# BSPD_5.net
KiCad netlist of a schematic drawn in EAGLE
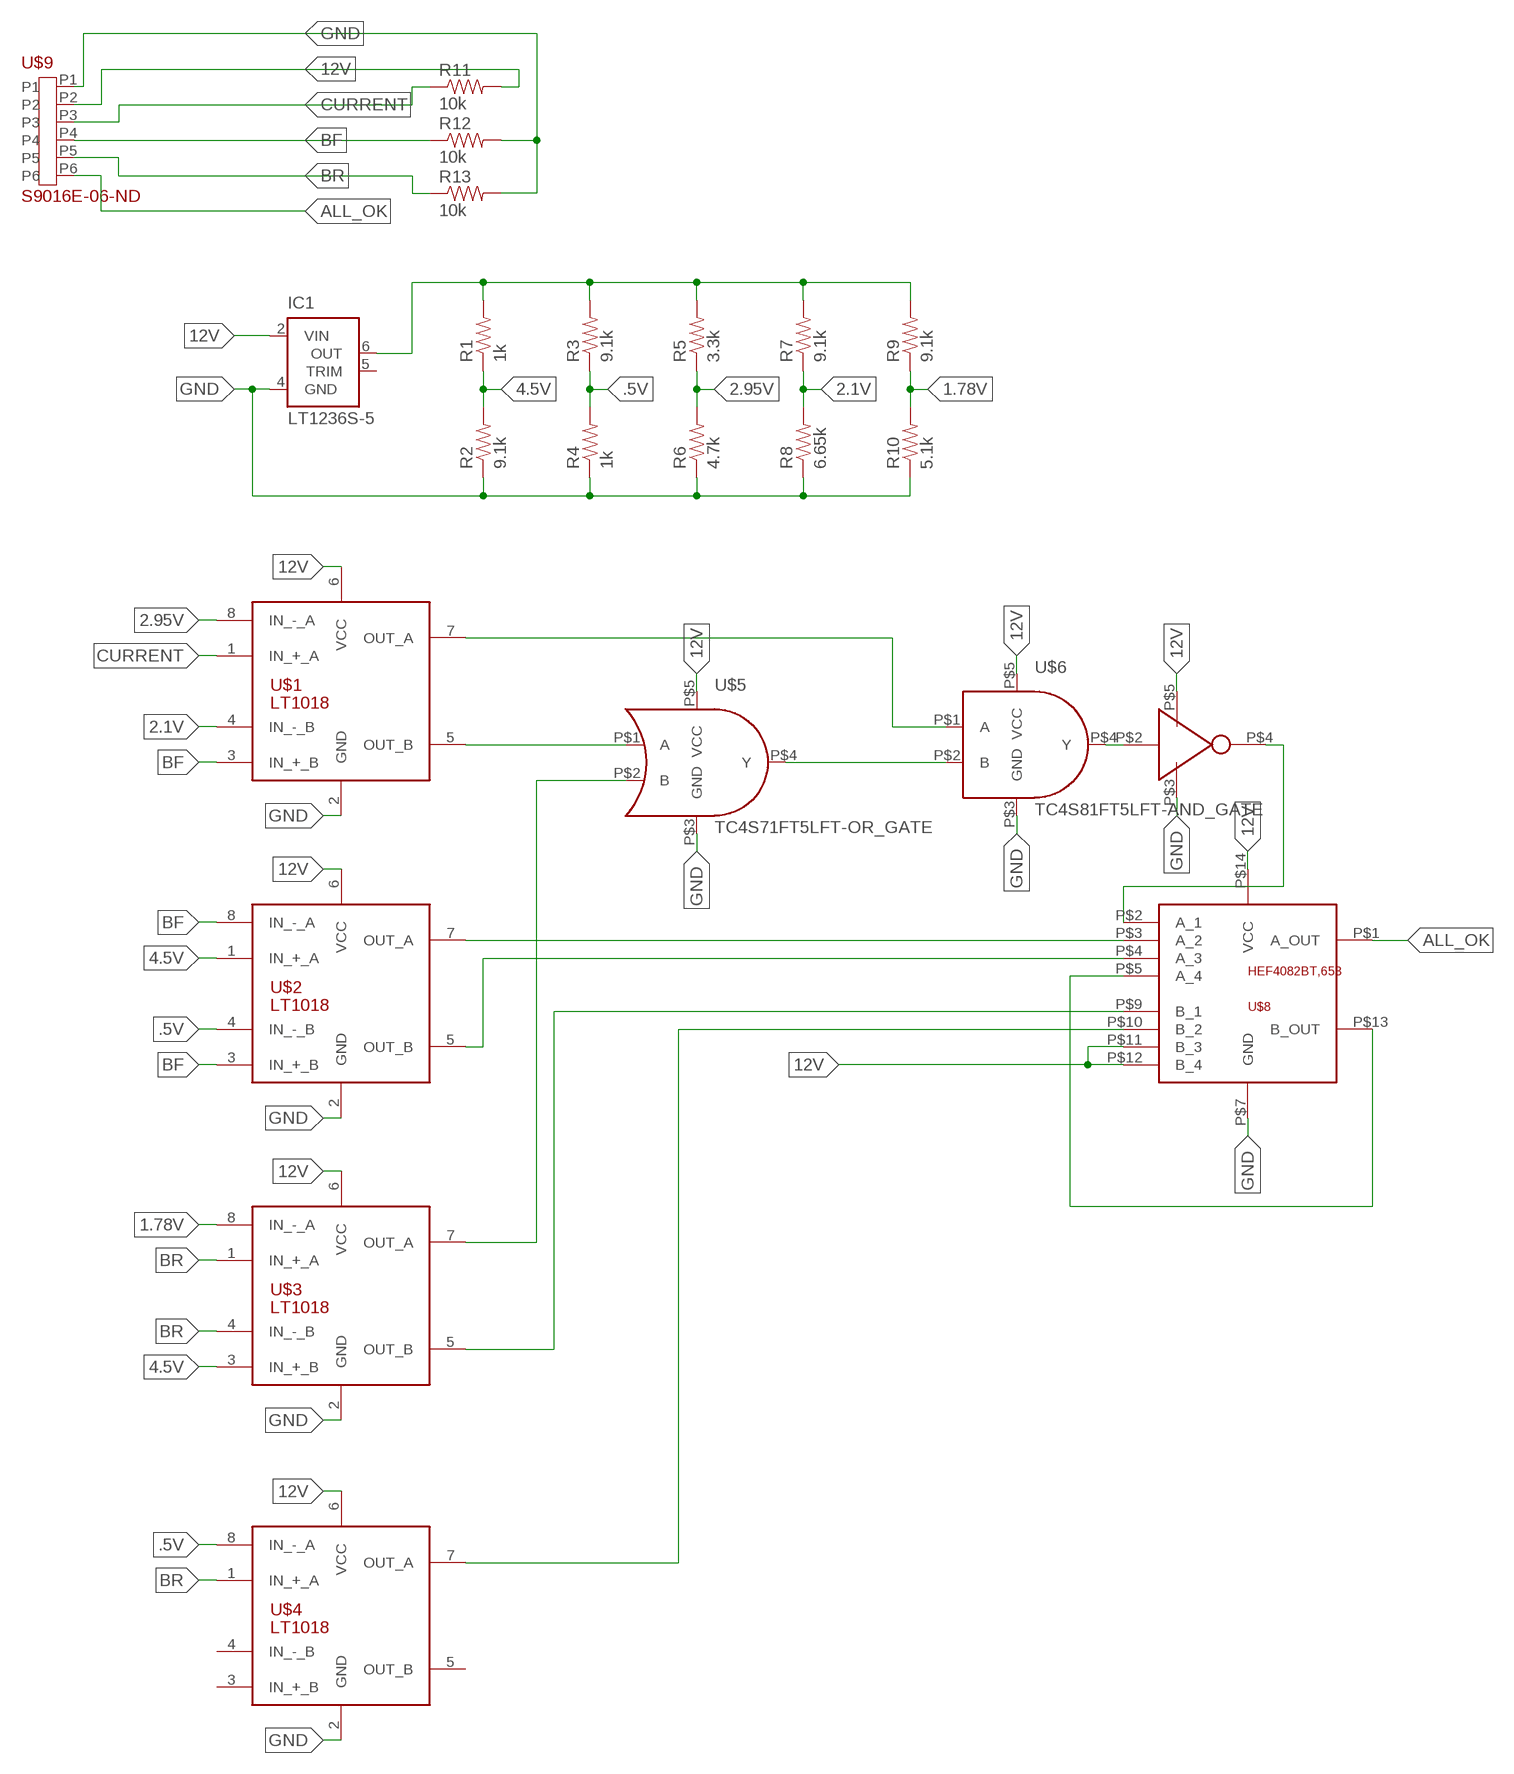
[diagram p0: schematic, sheet 1]

(export (version "E")
  (design (tool "Eeschema 10.0.6"))
  (components
    (comp (ref "IC1")
      (value "LT1236S-5")
      (footprint "eagle-import:SOIC8")
      (libsource (lib "eagle-import") (part "LT1236?S-5"))
    )
    (comp (ref "R1")
      (value "1k")
      (footprint "eagle-import:0603-RES")
      (libsource (lib "eagle-import") (part "RESISTOR0603"))
    )
    (comp (ref "R2")
      (value "9.1k")
      (footprint "eagle-import:0603-RES")
      (libsource (lib "eagle-import") (part "RESISTOR0603"))
    )
    (comp (ref "R3")
      (value "9.1k")
      (footprint "eagle-import:0603-RES")
      (libsource (lib "eagle-import") (part "RESISTOR0603"))
    )
    (comp (ref "R4")
      (value "1k")
      (footprint "eagle-import:0603-RES")
      (libsource (lib "eagle-import") (part "RESISTOR0603"))
    )
    (comp (ref "R5")
      (value "3.3k")
      (footprint "eagle-import:0603-RES")
      (libsource (lib "eagle-import") (part "RESISTOR0603"))
    )
    (comp (ref "R6")
      (value "4.7k")
      (footprint "eagle-import:0603-RES")
      (libsource (lib "eagle-import") (part "RESISTOR0603"))
    )
    (comp (ref "R7")
      (value "9.1k")
      (footprint "eagle-import:0603-RES")
      (libsource (lib "eagle-import") (part "RESISTOR0603"))
    )
    (comp (ref "R8")
      (value "6.65k")
      (footprint "eagle-import:0603-RES")
      (libsource (lib "eagle-import") (part "RESISTOR0603"))
    )
    (comp (ref "R9")
      (value "9.1k")
      (footprint "eagle-import:0603-RES")
      (libsource (lib "eagle-import") (part "RESISTOR0603"))
    )
    (comp (ref "R10")
      (value "5.1k")
      (footprint "eagle-import:0603-RES")
      (libsource (lib "eagle-import") (part "RESISTOR0603"))
    )
    (comp (ref "R11")
      (value "10k")
      (footprint "eagle-import:0603-RES")
      (libsource (lib "eagle-import") (part "RESISTOR0603"))
    )
    (comp (ref "R12")
      (value "10k")
      (footprint "eagle-import:0603-RES")
      (libsource (lib "eagle-import") (part "RESISTOR0603"))
    )
    (comp (ref "R13")
      (value "10k")
      (footprint "eagle-import:0603-RES")
      (libsource (lib "eagle-import") (part "RESISTOR0603"))
    )
    (comp (ref "U$1")
      (value "LT1018")
      (footprint "eagle-import:SOIC8")
      (libsource (lib "eagle-import") (part "LT1018"))
    )
    (comp (ref "U$2")
      (value "LT1018")
      (footprint "eagle-import:SOIC8")
      (libsource (lib "eagle-import") (part "LT1018"))
    )
    (comp (ref "U$3")
      (value "LT1018")
      (footprint "eagle-import:SOIC8")
      (libsource (lib "eagle-import") (part "LT1018"))
    )
    (comp (ref "U$4")
      (value "LT1018")
      (footprint "eagle-import:SOIC8")
      (libsource (lib "eagle-import") (part "LT1018"))
    )
    (comp (ref "U$5")
      (value "TC4S71FT5LFT-OR_GATE")
      (footprint "eagle-import:SSOP5-P-0.95")
      (libsource (lib "eagle-import") (part "TC4S71FT5LFT-OR_GATE"))
    )
    (comp (ref "U$6")
      (value "TC4S81FT5LFT-AND_GATE")
      (footprint "eagle-import:SSOP5-P-0.95")
      (libsource (lib "eagle-import") (part "TC4S81FT5LFT-AND_GATE"))
    )
    (comp (ref "U$7")
      (value "TC4S69F(TE85L,F)")
      (footprint "eagle-import:SSOP5-P-0.95")
      (libsource (lib "eagle-import") (part "TC4S69F(TE85L,F)"))
    )
    (comp (ref "U$8")
      (value "HEF4082BT,653")
      (footprint "eagle-import:NXP_14_SOIC")
      (libsource (lib "eagle-import") (part "HEF4082BT,653"))
    )
    (comp (ref "U$9")
      (value "S9016E-06-ND")
      (footprint "eagle-import:S9016E-05-ND")
      (libsource (lib "eagle-import") (part "S9016E-06-ND"))
    )
  )
  (nets
    (net (code "1") (name ".5V") (class "Default")
      (node (ref "R3") (pin "1") (pinfunction "1_1") (pintype "passive"))
      (node (ref "R4") (pin "2") (pinfunction "2_2") (pintype "passive"))
      (node (ref "U$2") (pin "4") (pinfunction "IN_-_B_4") (pintype "input"))
      (node (ref "U$4") (pin "8") (pinfunction "IN_-_A_8") (pintype "input"))
    )
    (net (code "2") (name "1.78V") (class "Default")
      (node (ref "R10") (pin "2") (pinfunction "2_2") (pintype "passive"))
      (node (ref "R9") (pin "1") (pinfunction "1_1") (pintype "passive"))
      (node (ref "U$3") (pin "8") (pinfunction "IN_-_A_8") (pintype "input"))
    )
    (net (code "3") (name "2.1V") (class "Default")
      (node (ref "R7") (pin "1") (pinfunction "1_1") (pintype "passive"))
      (node (ref "R8") (pin "2") (pinfunction "2_2") (pintype "passive"))
      (node (ref "U$1") (pin "4") (pinfunction "IN_-_B_4") (pintype "input"))
    )
    (net (code "4") (name "2.95V") (class "Default")
      (node (ref "R5") (pin "1") (pinfunction "1_1") (pintype "passive"))
      (node (ref "R6") (pin "2") (pinfunction "2_2") (pintype "passive"))
      (node (ref "U$1") (pin "8") (pinfunction "IN_-_A_8") (pintype "input"))
    )
    (net (code "5") (name "4.5V") (class "Default")
      (node (ref "R1") (pin "1") (pinfunction "1_1") (pintype "passive"))
      (node (ref "R2") (pin "2") (pinfunction "2_2") (pintype "passive"))
      (node (ref "U$2") (pin "1") (pinfunction "IN_+_A_1") (pintype "input"))
      (node (ref "U$3") (pin "3") (pinfunction "IN_+_B_3") (pintype "input"))
    )
    (net (code "6") (name "12V") (class "Default")
      (node (ref "IC1") (pin "2") (pinfunction "VIN_2") (pintype "input"))
      (node (ref "R11") (pin "2") (pinfunction "2_2") (pintype "passive"))
      (node (ref "U$1") (pin "6") (pinfunction "VCC_6") (pintype "power_in"))
      (node (ref "U$2") (pin "6") (pinfunction "VCC_6") (pintype "power_in"))
      (node (ref "U$3") (pin "6") (pinfunction "VCC_6") (pintype "power_in"))
      (node (ref "U$4") (pin "6") (pinfunction "VCC_6") (pintype "power_in"))
      (node (ref "U$5") (pin "P$5") (pinfunction "VCC_P$5") (pintype "bidirectional"))
      (node (ref "U$6") (pin "P$5") (pinfunction "VCC_P$5") (pintype "bidirectional"))
      (node (ref "U$7") (pin "P$5") (pinfunction "VCC_P$5") (pintype "power_in"))
      (node (ref "U$8") (pin "P$11") (pinfunction "B_3_P$11") (pintype "open_collector"))
      (node (ref "U$8") (pin "P$12") (pinfunction "B_4_P$12") (pintype "open_collector"))
      (node (ref "U$8") (pin "P$14") (pinfunction "VCC_P$14") (pintype "power_in"))
      (node (ref "U$9") (pin "P2") (pinfunction "P2_P2") (pintype "bidirectional"))
    )
    (net (code "7") (name "ALL_OK") (class "Default")
      (node (ref "U$8") (pin "P$1") (pinfunction "A_OUT_P$1") (pintype "output"))
      (node (ref "U$9") (pin "P6") (pinfunction "P6_P6") (pintype "bidirectional"))
    )
    (net (code "8") (name "BF") (class "Default")
      (node (ref "R12") (pin "1") (pinfunction "1_1") (pintype "passive"))
      (node (ref "U$1") (pin "3") (pinfunction "IN_+_B_3") (pintype "input"))
      (node (ref "U$2") (pin "3") (pinfunction "IN_+_B_3") (pintype "input"))
      (node (ref "U$2") (pin "8") (pinfunction "IN_-_A_8") (pintype "input"))
      (node (ref "U$9") (pin "P4") (pinfunction "P4_P4") (pintype "bidirectional"))
    )
    (net (code "9") (name "BR") (class "Default")
      (node (ref "R13") (pin "1") (pinfunction "1_1") (pintype "passive"))
      (node (ref "U$3") (pin "1") (pinfunction "IN_+_A_1") (pintype "input"))
      (node (ref "U$3") (pin "4") (pinfunction "IN_-_B_4") (pintype "input"))
      (node (ref "U$4") (pin "1") (pinfunction "IN_+_A_1") (pintype "input"))
      (node (ref "U$9") (pin "P5") (pinfunction "P5_P5") (pintype "bidirectional"))
    )
    (net (code "10") (name "CURRENT") (class "Default")
      (node (ref "R11") (pin "1") (pinfunction "1_1") (pintype "passive"))
      (node (ref "U$1") (pin "1") (pinfunction "IN_+_A_1") (pintype "input"))
      (node (ref "U$9") (pin "P3") (pinfunction "P3_P3") (pintype "bidirectional"))
    )
    (net (code "11") (name "GND") (class "Default")
      (node (ref "IC1") (pin "4") (pinfunction "GND_4") (pintype "power_in"))
      (node (ref "R10") (pin "1") (pinfunction "1_1") (pintype "passive"))
      (node (ref "R12") (pin "2") (pinfunction "2_2") (pintype "passive"))
      (node (ref "R13") (pin "2") (pinfunction "2_2") (pintype "passive"))
      (node (ref "R2") (pin "1") (pinfunction "1_1") (pintype "passive"))
      (node (ref "R4") (pin "1") (pinfunction "1_1") (pintype "passive"))
      (node (ref "R6") (pin "1") (pinfunction "1_1") (pintype "passive"))
      (node (ref "R8") (pin "1") (pinfunction "1_1") (pintype "passive"))
      (node (ref "U$1") (pin "2") (pinfunction "GND_2") (pintype "power_in"))
      (node (ref "U$2") (pin "2") (pinfunction "GND_2") (pintype "power_in"))
      (node (ref "U$3") (pin "2") (pinfunction "GND_2") (pintype "power_in"))
      (node (ref "U$4") (pin "2") (pinfunction "GND_2") (pintype "power_in"))
      (node (ref "U$5") (pin "P$3") (pinfunction "GND_P$3") (pintype "bidirectional"))
      (node (ref "U$6") (pin "P$3") (pinfunction "GND_P$3") (pintype "bidirectional"))
      (node (ref "U$7") (pin "P$3") (pinfunction "GND_P$3") (pintype "power_in"))
      (node (ref "U$8") (pin "P$7") (pinfunction "GND_P$7") (pintype "power_in"))
      (node (ref "U$9") (pin "P1") (pinfunction "P1_P1") (pintype "bidirectional"))
    )
    (net (code "12") (name "Net-(IC1-OUT)") (class "Default")
      (node (ref "IC1") (pin "6") (pinfunction "OUT_6") (pintype "input"))
      (node (ref "R1") (pin "2") (pinfunction "2_2") (pintype "passive"))
      (node (ref "R3") (pin "2") (pinfunction "2_2") (pintype "passive"))
      (node (ref "R5") (pin "2") (pinfunction "2_2") (pintype "passive"))
      (node (ref "R7") (pin "2") (pinfunction "2_2") (pintype "passive"))
      (node (ref "R9") (pin "2") (pinfunction "2_2") (pintype "passive"))
    )
    (net (code "13") (name "Net-(U$1-OUT_A)") (class "Default")
      (node (ref "U$1") (pin "7") (pinfunction "OUT_A_7") (pintype "output"))
      (node (ref "U$6") (pin "P$1") (pinfunction "A_P$1") (pintype "bidirectional"))
    )
    (net (code "14") (name "Net-(U$1-OUT_B)") (class "Default")
      (node (ref "U$1") (pin "5") (pinfunction "OUT_B_5") (pintype "output"))
      (node (ref "U$5") (pin "P$1") (pinfunction "A_P$1") (pintype "bidirectional"))
    )
    (net (code "15") (name "Net-(U$2-OUT_A)") (class "Default")
      (node (ref "U$2") (pin "7") (pinfunction "OUT_A_7") (pintype "output"))
      (node (ref "U$8") (pin "P$3") (pinfunction "A_2_P$3") (pintype "open_collector"))
    )
    (net (code "16") (name "Net-(U$2-OUT_B)") (class "Default")
      (node (ref "U$2") (pin "5") (pinfunction "OUT_B_5") (pintype "output"))
      (node (ref "U$8") (pin "P$4") (pinfunction "A_3_P$4") (pintype "open_collector"))
    )
    (net (code "17") (name "Net-(U$3-OUT_A)") (class "Default")
      (node (ref "U$3") (pin "7") (pinfunction "OUT_A_7") (pintype "output"))
      (node (ref "U$5") (pin "P$2") (pinfunction "B_P$2") (pintype "bidirectional"))
    )
    (net (code "18") (name "Net-(U$3-OUT_B)") (class "Default")
      (node (ref "U$3") (pin "5") (pinfunction "OUT_B_5") (pintype "output"))
      (node (ref "U$8") (pin "P$9") (pinfunction "B_1_P$9") (pintype "open_collector"))
    )
    (net (code "19") (name "Net-(U$4-OUT_A)") (class "Default")
      (node (ref "U$4") (pin "7") (pinfunction "OUT_A_7") (pintype "output"))
      (node (ref "U$8") (pin "P$10") (pinfunction "B_2_P$10") (pintype "open_collector"))
    )
    (net (code "20") (name "Net-(U$5-Y)") (class "Default")
      (node (ref "U$5") (pin "P$4") (pinfunction "Y_P$4") (pintype "bidirectional"))
      (node (ref "U$6") (pin "P$2") (pinfunction "B_P$2") (pintype "bidirectional"))
    )
    (net (code "21") (name "Net-(U$6-Y)") (class "Default")
      (node (ref "U$6") (pin "P$4") (pinfunction "Y_P$4") (pintype "bidirectional"))
      (node (ref "U$7") (pin "P$2") (pinfunction "IN_P$2") (pintype "input"))
    )
    (net (code "22") (name "Net-(U$7-OUT)") (class "Default")
      (node (ref "U$7") (pin "P$4") (pinfunction "OUT_P$4") (pintype "output"))
      (node (ref "U$8") (pin "P$2") (pinfunction "A_1_P$2") (pintype "open_collector"))
    )
    (net (code "23") (name "Net-(U$8-A_4)") (class "Default")
      (node (ref "U$8") (pin "P$13") (pinfunction "B_OUT_P$13") (pintype "output"))
      (node (ref "U$8") (pin "P$5") (pinfunction "A_4_P$5") (pintype "open_collector"))
    )
    (net (code "24") (name "unconnected-(IC1-TRIM-Pad5)") (class "Default")
      (node (ref "IC1") (pin "5") (pinfunction "TRIM_5") (pintype "passive"))
    )
    (net (code "25") (name "unconnected-(U$4-IN_+_B-Pad3)") (class "Default")
      (node (ref "U$4") (pin "3") (pinfunction "IN_+_B_3") (pintype "input"))
    )
    (net (code "26") (name "unconnected-(U$4-IN_-_B-Pad4)") (class "Default")
      (node (ref "U$4") (pin "4") (pinfunction "IN_-_B_4") (pintype "input"))
    )
    (net (code "27") (name "unconnected-(U$4-OUT_B-Pad5)") (class "Default")
      (node (ref "U$4") (pin "5") (pinfunction "OUT_B_5") (pintype "output"))
    )
  )
)
